# Irrigatron.net
KiCad netlist of a schematic drawn in EasyEDA
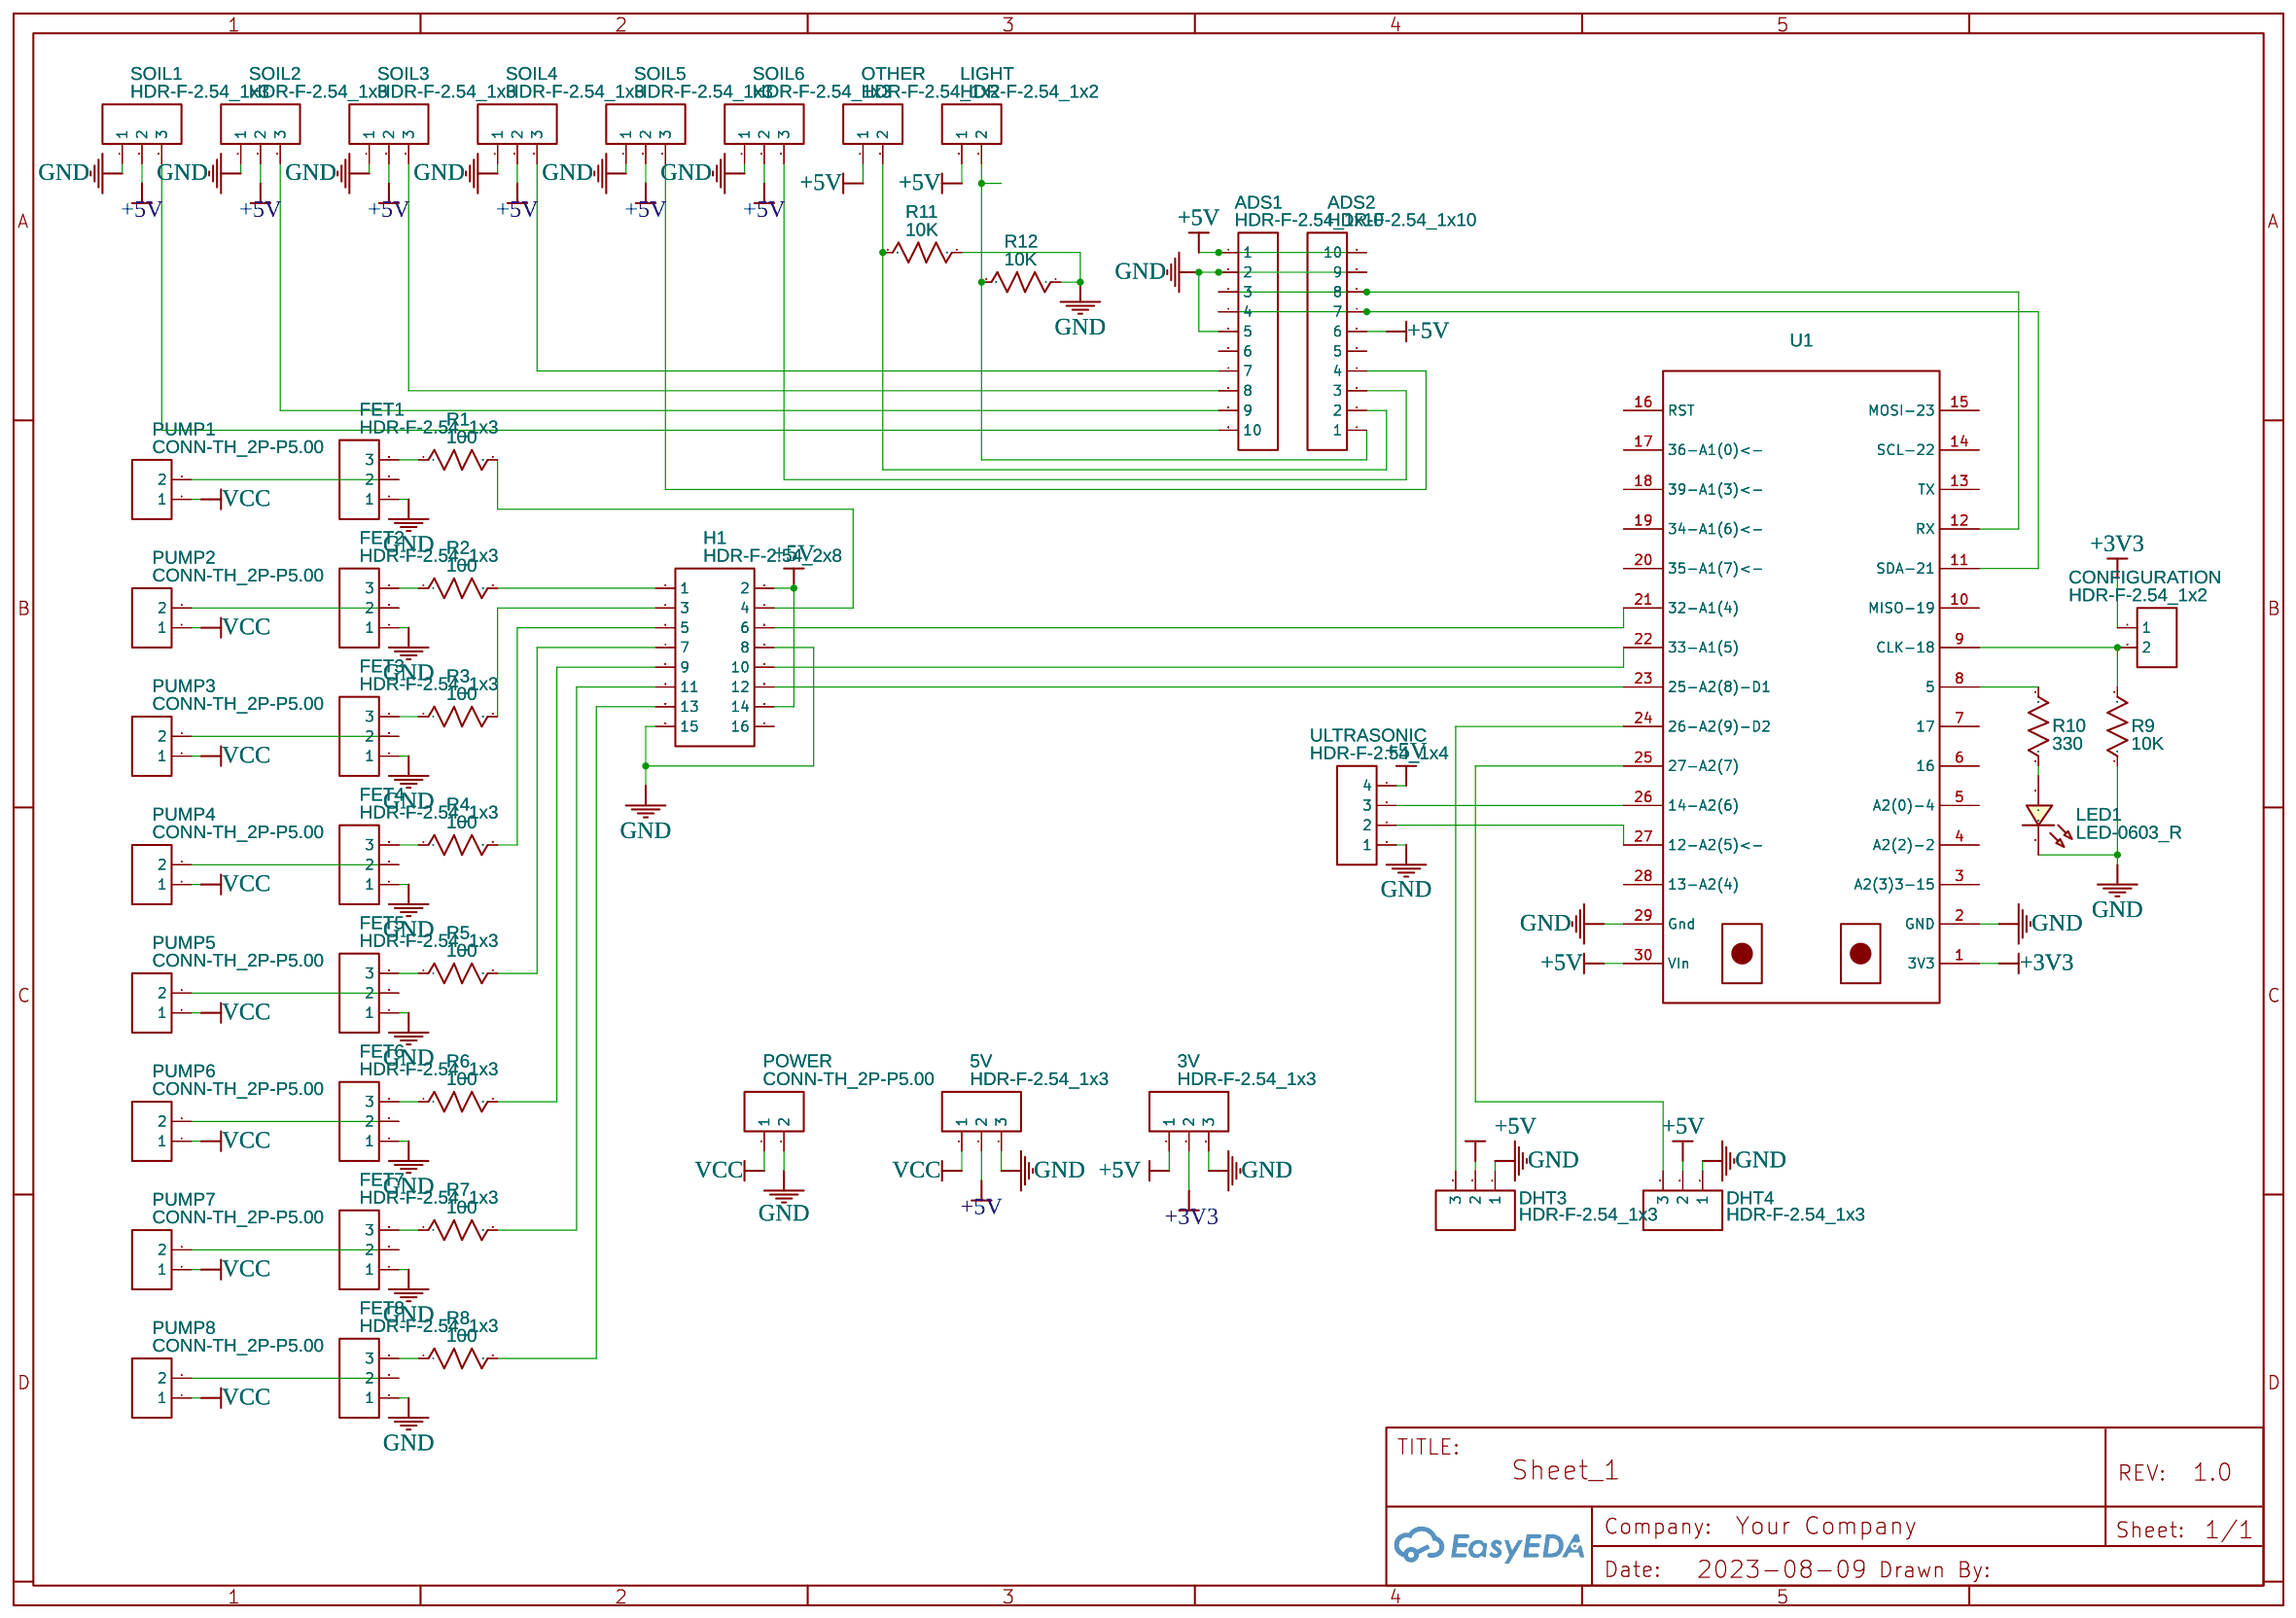
[diagram p0: schematic sheet]

(export (version "E")
  (design (tool "Eeschema 10.0.6"))
  (components
    (comp (ref "3V") (value "HDR-F-2.54_1x3") (libsource (lib "") (part "HDR-F-2.54_1x3_4")))
    (comp (ref "5V") (value "HDR-F-2.54_1x3") (libsource (lib "") (part "HDR-F-2.54_1x3_3")))
    (comp (ref "ADS1") (value "HDR-F-2.54_1x10") (libsource (lib "") (part "HDR-F-2.54_1x10")))
    (comp (ref "ADS2") (value "HDR-F-2.54_1x10") (libsource (lib "") (part "HDR-F-2.54_1x10_1")))
    (comp (ref "CONFIGURATION") (value "HDR-F-2.54_1x2") (libsource (lib "") (part "HDR-F-2.54_1x2_1")))
    (comp (ref "DHT3") (value "HDR-F-2.54_1x3") (libsource (lib "") (part "HDR-F-2.54_1x3")))
    (comp (ref "DHT4") (value "HDR-F-2.54_1x3") (libsource (lib "") (part "HDR-F-2.54_1x3")))
    (comp (ref "FET1") (value "HDR-F-2.54_1x3") (libsource (lib "") (part "HDR-F-2.54_1x3_1")))
    (comp (ref "FET2") (value "HDR-F-2.54_1x3") (libsource (lib "") (part "HDR-F-2.54_1x3_1")))
    (comp (ref "FET3") (value "HDR-F-2.54_1x3") (libsource (lib "") (part "HDR-F-2.54_1x3_1")))
    (comp (ref "FET4") (value "HDR-F-2.54_1x3") (libsource (lib "") (part "HDR-F-2.54_1x3_1")))
    (comp (ref "FET5") (value "HDR-F-2.54_1x3") (libsource (lib "") (part "HDR-F-2.54_1x3_1")))
    (comp (ref "FET6") (value "HDR-F-2.54_1x3") (libsource (lib "") (part "HDR-F-2.54_1x3_1")))
    (comp (ref "FET7") (value "HDR-F-2.54_1x3") (libsource (lib "") (part "HDR-F-2.54_1x3_1")))
    (comp (ref "FET8") (value "HDR-F-2.54_1x3") (libsource (lib "") (part "HDR-F-2.54_1x3_1")))
    (comp (ref "H1") (value "HDR-F-2.54_2x8") (libsource (lib "") (part "HDR-F-2.54_2x8")))
    (comp (ref "LED1")
      (value "LED-0603_R")
      (fields
        (field (name "Manufacturer Part") "19-217/R6C-AL1M2VY/3T")
        (field (name "Manufacturer") "EVERLIGHT(台湾亿光)")
      )
      (libsource (lib "") (part "LED-0603_R"))
    )
    (comp (ref "LIGHT") (value "HDR-F-2.54_1x2") (libsource (lib "") (part "HDR-F-2.54_1x2")))
    (comp (ref "OTHER") (value "HDR-F-2.54_1x2") (libsource (lib "") (part "HDR-F-2.54_1x2_2")))
    (comp (ref "POWER") (value "CONN-TH_2P-P5.00") (libsource (lib "") (part "CONN-TH_2P-P5.00_1")))
    (comp (ref "PUMP1") (value "CONN-TH_2P-P5.00") (libsource (lib "") (part "CONN-TH_2P-P5.00")))
    (comp (ref "PUMP2") (value "CONN-TH_2P-P5.00") (libsource (lib "") (part "CONN-TH_2P-P5.00")))
    (comp (ref "PUMP3") (value "CONN-TH_2P-P5.00") (libsource (lib "") (part "CONN-TH_2P-P5.00")))
    (comp (ref "PUMP4") (value "CONN-TH_2P-P5.00") (libsource (lib "") (part "CONN-TH_2P-P5.00")))
    (comp (ref "PUMP5") (value "CONN-TH_2P-P5.00") (libsource (lib "") (part "CONN-TH_2P-P5.00")))
    (comp (ref "PUMP6") (value "CONN-TH_2P-P5.00") (libsource (lib "") (part "CONN-TH_2P-P5.00")))
    (comp (ref "PUMP7") (value "CONN-TH_2P-P5.00") (libsource (lib "") (part "CONN-TH_2P-P5.00")))
    (comp (ref "PUMP8") (value "CONN-TH_2P-P5.00") (libsource (lib "") (part "CONN-TH_2P-P5.00")))
    (comp (ref "R1") (value "100") (libsource (lib "") (part "R_0603_US_2")))
    (comp (ref "R2") (value "100") (libsource (lib "") (part "R_0603_US_2")))
    (comp (ref "R3") (value "100") (libsource (lib "") (part "R_0603_US_2")))
    (comp (ref "R4") (value "100") (libsource (lib "") (part "R_0603_US_2")))
    (comp (ref "R5") (value "100") (libsource (lib "") (part "R_0603_US_2")))
    (comp (ref "R6") (value "100") (libsource (lib "") (part "R_0603_US_2")))
    (comp (ref "R7") (value "100") (libsource (lib "") (part "R_0603_US_2")))
    (comp (ref "R8") (value "100") (libsource (lib "") (part "R_0603_US_2")))
    (comp (ref "R9") (value "10K") (libsource (lib "") (part "R_0603_US")))
    (comp (ref "R10") (value "330") (libsource (lib "") (part "R_0603_US")))
    (comp (ref "R11") (value "10K") (libsource (lib "") (part "R_0603_US_1")))
    (comp (ref "R12") (value "10K") (libsource (lib "") (part "R_0603_US_1")))
    (comp (ref "SOIL1") (value "HDR-F-2.54_1x3") (libsource (lib "") (part "HDR-F-2.54_1x3_2")))
    (comp (ref "SOIL2") (value "HDR-F-2.54_1x3") (libsource (lib "") (part "HDR-F-2.54_1x3_2")))
    (comp (ref "SOIL3") (value "HDR-F-2.54_1x3") (libsource (lib "") (part "HDR-F-2.54_1x3_2")))
    (comp (ref "SOIL4") (value "HDR-F-2.54_1x3") (libsource (lib "") (part "HDR-F-2.54_1x3_2")))
    (comp (ref "SOIL5") (value "HDR-F-2.54_1x3") (libsource (lib "") (part "HDR-F-2.54_1x3_2")))
    (comp (ref "SOIL6") (value "HDR-F-2.54_1x3") (libsource (lib "") (part "HDR-F-2.54_1x3_2")))
    (comp (ref "U1") (value "NO") (libsource (lib "") (part "DOIT ESP32 DEVKIT V1 (30pins)")))
    (comp (ref "ULTRASONIC") (value "HDR-F-2.54_1x4") (libsource (lib "") (part "HDR-F-2.54_1x4")))
  )
  (nets
    (net (code "1") (name "+3V3") (class "Default")
      (node (ref "3V") (pin "2") (pinfunction "2_2") (pintype "input"))
      (node (ref "CONFIGURATION") (pin "1") (pinfunction "1_1") (pintype "input"))
      (node (ref "U1") (pin "1") (pinfunction "3V3_1") (pintype "unspecified"))
    )
    (net (code "2") (name "+5V") (class "Default")
      (node (ref "3V") (pin "1") (pinfunction "1_1") (pintype "input"))
      (node (ref "5V") (pin "2") (pinfunction "2_2") (pintype "input"))
      (node (ref "ADS1") (pin "1") (pinfunction "1_1") (pintype "unspecified"))
      (node (ref "ADS2") (pin "10") (pinfunction "10_10") (pintype "unspecified"))
      (node (ref "ADS2") (pin "6") (pinfunction "6_6") (pintype "unspecified"))
      (node (ref "DHT3") (pin "2") (pinfunction "2_2") (pintype "input"))
      (node (ref "DHT4") (pin "2") (pinfunction "2_2") (pintype "input"))
      (node (ref "H1") (pin "14") (pinfunction "14_14") (pintype "input"))
      (node (ref "H1") (pin "2") (pinfunction "2_2") (pintype "input"))
      (node (ref "LIGHT") (pin "1") (pinfunction "1_1") (pintype "input"))
      (node (ref "OTHER") (pin "1") (pinfunction "1_1") (pintype "input"))
      (node (ref "SOIL1") (pin "2") (pinfunction "2_2") (pintype "input"))
      (node (ref "SOIL2") (pin "2") (pinfunction "2_2") (pintype "input"))
      (node (ref "SOIL3") (pin "2") (pinfunction "2_2") (pintype "input"))
      (node (ref "SOIL4") (pin "2") (pinfunction "2_2") (pintype "input"))
      (node (ref "SOIL5") (pin "2") (pinfunction "2_2") (pintype "input"))
      (node (ref "SOIL6") (pin "2") (pinfunction "2_2") (pintype "input"))
      (node (ref "U1") (pin "30") (pinfunction "VIn_30") (pintype "unspecified"))
      (node (ref "ULTRASONIC") (pin "4") (pinfunction "4_4") (pintype "unspecified"))
    )
    (net (code "3") (name "GND") (class "Default")
      (node (ref "3V") (pin "3") (pinfunction "3_3") (pintype "input"))
      (node (ref "5V") (pin "3") (pinfunction "3_3") (pintype "input"))
      (node (ref "ADS1") (pin "2") (pinfunction "2_2") (pintype "unspecified"))
      (node (ref "ADS1") (pin "5") (pinfunction "5_5") (pintype "unspecified"))
      (node (ref "ADS2") (pin "9") (pinfunction "9_9") (pintype "unspecified"))
      (node (ref "DHT3") (pin "1") (pinfunction "1_1") (pintype "input"))
      (node (ref "DHT4") (pin "1") (pinfunction "1_1") (pintype "input"))
      (node (ref "FET1") (pin "1") (pinfunction "1_1") (pintype "input"))
      (node (ref "FET2") (pin "1") (pinfunction "1_1") (pintype "input"))
      (node (ref "FET3") (pin "1") (pinfunction "1_1") (pintype "input"))
      (node (ref "FET4") (pin "1") (pinfunction "1_1") (pintype "input"))
      (node (ref "FET5") (pin "1") (pinfunction "1_1") (pintype "input"))
      (node (ref "FET6") (pin "1") (pinfunction "1_1") (pintype "input"))
      (node (ref "FET7") (pin "1") (pinfunction "1_1") (pintype "input"))
      (node (ref "FET8") (pin "1") (pinfunction "1_1") (pintype "input"))
      (node (ref "H1") (pin "15") (pinfunction "15_15") (pintype "input"))
      (node (ref "H1") (pin "8") (pinfunction "8_8") (pintype "input"))
      (node (ref "LED1") (pin "2") (pinfunction "2_2") (pintype "unspecified"))
      (node (ref "POWER") (pin "2") (pinfunction "2_2") (pintype "unspecified"))
      (node (ref "R11") (pin "1") (pinfunction "1_1") (pintype "unspecified"))
      (node (ref "R12") (pin "1") (pinfunction "1_1") (pintype "unspecified"))
      (node (ref "R9") (pin "1") (pinfunction "1_1") (pintype "unspecified"))
      (node (ref "SOIL1") (pin "1") (pinfunction "1_1") (pintype "input"))
      (node (ref "SOIL2") (pin "1") (pinfunction "1_1") (pintype "input"))
      (node (ref "SOIL3") (pin "1") (pinfunction "1_1") (pintype "input"))
      (node (ref "SOIL4") (pin "1") (pinfunction "1_1") (pintype "input"))
      (node (ref "SOIL5") (pin "1") (pinfunction "1_1") (pintype "input"))
      (node (ref "SOIL6") (pin "1") (pinfunction "1_1") (pintype "input"))
      (node (ref "U1") (pin "2") (pinfunction "GND_2") (pintype "unspecified"))
      (node (ref "U1") (pin "29") (pinfunction "Gnd_29") (pintype "unspecified"))
      (node (ref "ULTRASONIC") (pin "1") (pinfunction "1_1") (pintype "unspecified"))
    )
    (net (code "4") (name "Net-(ADS1-Pad7)") (class "Default")
      (node (ref "ADS1") (pin "7") (pinfunction "7_7") (pintype "unspecified"))
      (node (ref "SOIL4") (pin "3") (pinfunction "3_3") (pintype "input"))
    )
    (net (code "5") (name "Net-(ADS1-Pad8)") (class "Default")
      (node (ref "ADS1") (pin "8") (pinfunction "8_8") (pintype "unspecified"))
      (node (ref "SOIL3") (pin "3") (pinfunction "3_3") (pintype "input"))
    )
    (net (code "6") (name "Net-(ADS1-Pad9)") (class "Default")
      (node (ref "ADS1") (pin "9") (pinfunction "9_9") (pintype "unspecified"))
      (node (ref "SOIL2") (pin "3") (pinfunction "3_3") (pintype "input"))
    )
    (net (code "7") (name "Net-(ADS1-Pad10)") (class "Default")
      (node (ref "ADS1") (pin "10") (pinfunction "10_10") (pintype "unspecified"))
      (node (ref "SOIL1") (pin "3") (pinfunction "3_3") (pintype "input"))
    )
    (net (code "8") (name "Net-(ADS2-Pad1)") (class "Default")
      (node (ref "ADS2") (pin "1") (pinfunction "1_1") (pintype "unspecified"))
      (node (ref "LIGHT") (pin "2") (pinfunction "2_2") (pintype "input"))
      (node (ref "R12") (pin "2") (pinfunction "2_2") (pintype "unspecified"))
    )
    (net (code "9") (name "Net-(ADS2-Pad2)") (class "Default")
      (node (ref "ADS2") (pin "2") (pinfunction "2_2") (pintype "unspecified"))
      (node (ref "OTHER") (pin "2") (pinfunction "2_2") (pintype "input"))
      (node (ref "R11") (pin "2") (pinfunction "2_2") (pintype "unspecified"))
    )
    (net (code "10") (name "Net-(ADS2-Pad3)") (class "Default")
      (node (ref "ADS2") (pin "3") (pinfunction "3_3") (pintype "unspecified"))
      (node (ref "SOIL6") (pin "3") (pinfunction "3_3") (pintype "input"))
    )
    (net (code "11") (name "Net-(ADS2-Pad4)") (class "Default")
      (node (ref "ADS2") (pin "4") (pinfunction "4_4") (pintype "unspecified"))
      (node (ref "SOIL5") (pin "3") (pinfunction "3_3") (pintype "input"))
    )
    (net (code "12") (name "Net-(FET1-Pad2)") (class "Default")
      (node (ref "FET1") (pin "2") (pinfunction "2_2") (pintype "input"))
      (node (ref "PUMP1") (pin "2") (pinfunction "2_2") (pintype "unspecified"))
    )
    (net (code "13") (name "Net-(FET1-Pad3)") (class "Default")
      (node (ref "FET1") (pin "3") (pinfunction "3_3") (pintype "input"))
      (node (ref "R1") (pin "1") (pinfunction "1_1") (pintype "unspecified"))
    )
    (net (code "14") (name "Net-(FET2-Pad2)") (class "Default")
      (node (ref "FET2") (pin "2") (pinfunction "2_2") (pintype "input"))
      (node (ref "PUMP2") (pin "2") (pinfunction "2_2") (pintype "unspecified"))
    )
    (net (code "15") (name "Net-(FET2-Pad3)") (class "Default")
      (node (ref "FET2") (pin "3") (pinfunction "3_3") (pintype "input"))
      (node (ref "R2") (pin "1") (pinfunction "1_1") (pintype "unspecified"))
    )
    (net (code "16") (name "Net-(FET3-Pad3)") (class "Default")
      (node (ref "FET3") (pin "3") (pinfunction "3_3") (pintype "input"))
      (node (ref "R3") (pin "1") (pinfunction "1_1") (pintype "unspecified"))
    )
    (net (code "17") (name "Net-(FET4-Pad2)") (class "Default")
      (node (ref "FET4") (pin "2") (pinfunction "2_2") (pintype "input"))
      (node (ref "PUMP4") (pin "2") (pinfunction "2_2") (pintype "unspecified"))
    )
    (net (code "18") (name "Net-(FET4-Pad3)") (class "Default")
      (node (ref "FET4") (pin "3") (pinfunction "3_3") (pintype "input"))
      (node (ref "R4") (pin "1") (pinfunction "1_1") (pintype "unspecified"))
    )
    (net (code "19") (name "Net-(FET5-Pad2)") (class "Default")
      (node (ref "FET5") (pin "2") (pinfunction "2_2") (pintype "input"))
      (node (ref "PUMP5") (pin "2") (pinfunction "2_2") (pintype "unspecified"))
    )
    (net (code "20") (name "Net-(FET5-Pad3)") (class "Default")
      (node (ref "FET5") (pin "3") (pinfunction "3_3") (pintype "input"))
      (node (ref "R5") (pin "1") (pinfunction "1_1") (pintype "unspecified"))
    )
    (net (code "21") (name "Net-(FET6-Pad2)") (class "Default")
      (node (ref "FET6") (pin "2") (pinfunction "2_2") (pintype "input"))
      (node (ref "PUMP6") (pin "2") (pinfunction "2_2") (pintype "unspecified"))
    )
    (net (code "22") (name "Net-(FET6-Pad3)") (class "Default")
      (node (ref "FET6") (pin "3") (pinfunction "3_3") (pintype "input"))
      (node (ref "R6") (pin "1") (pinfunction "1_1") (pintype "unspecified"))
    )
    (net (code "23") (name "Net-(FET7-Pad2)") (class "Default")
      (node (ref "FET7") (pin "2") (pinfunction "2_2") (pintype "input"))
      (node (ref "PUMP7") (pin "2") (pinfunction "2_2") (pintype "unspecified"))
    )
    (net (code "24") (name "Net-(FET7-Pad3)") (class "Default")
      (node (ref "FET7") (pin "3") (pinfunction "3_3") (pintype "input"))
      (node (ref "R7") (pin "1") (pinfunction "1_1") (pintype "unspecified"))
    )
    (net (code "25") (name "Net-(FET8-Pad2)") (class "Default")
      (node (ref "FET8") (pin "2") (pinfunction "2_2") (pintype "input"))
      (node (ref "PUMP8") (pin "2") (pinfunction "2_2") (pintype "unspecified"))
    )
    (net (code "26") (name "Net-(FET8-Pad3)") (class "Default")
      (node (ref "FET8") (pin "3") (pinfunction "3_3") (pintype "input"))
      (node (ref "R8") (pin "1") (pinfunction "1_1") (pintype "unspecified"))
    )
    (net (code "27") (name "Net-(H1-Pad1)") (class "Default")
      (node (ref "H1") (pin "1") (pinfunction "1_1") (pintype "input"))
      (node (ref "R2") (pin "2") (pinfunction "2_2") (pintype "unspecified"))
    )
    (net (code "28") (name "Net-(H1-Pad3)") (class "Default")
      (node (ref "H1") (pin "3") (pinfunction "3_3") (pintype "input"))
      (node (ref "R3") (pin "2") (pinfunction "2_2") (pintype "unspecified"))
    )
    (net (code "29") (name "Net-(H1-Pad4)") (class "Default")
      (node (ref "H1") (pin "4") (pinfunction "4_4") (pintype "input"))
      (node (ref "R1") (pin "2") (pinfunction "2_2") (pintype "unspecified"))
    )
    (net (code "30") (name "Net-(H1-Pad5)") (class "Default")
      (node (ref "H1") (pin "5") (pinfunction "5_5") (pintype "input"))
      (node (ref "R4") (pin "2") (pinfunction "2_2") (pintype "unspecified"))
    )
    (net (code "31") (name "Net-(H1-Pad7)") (class "Default")
      (node (ref "H1") (pin "7") (pinfunction "7_7") (pintype "input"))
      (node (ref "R5") (pin "2") (pinfunction "2_2") (pintype "unspecified"))
    )
    (net (code "32") (name "Net-(H1-Pad9)") (class "Default")
      (node (ref "H1") (pin "9") (pinfunction "9_9") (pintype "input"))
      (node (ref "R6") (pin "2") (pinfunction "2_2") (pintype "unspecified"))
    )
    (net (code "33") (name "Net-(H1-Pad11)") (class "Default")
      (node (ref "H1") (pin "11") (pinfunction "11_11") (pintype "input"))
      (node (ref "R7") (pin "2") (pinfunction "2_2") (pintype "unspecified"))
    )
    (net (code "34") (name "Net-(H1-Pad13)") (class "Default")
      (node (ref "H1") (pin "13") (pinfunction "13_13") (pintype "input"))
      (node (ref "R8") (pin "2") (pinfunction "2_2") (pintype "unspecified"))
    )
    (net (code "35") (name "Net-(LED1-Pad1)") (class "Default")
      (node (ref "LED1") (pin "1") (pinfunction "1_1") (pintype "unspecified"))
      (node (ref "R10") (pin "1") (pinfunction "1_1") (pintype "unspecified"))
    )
    (net (code "36") (name "Net-(U1-5)") (class "Default")
      (node (ref "R10") (pin "2") (pinfunction "2_2") (pintype "unspecified"))
      (node (ref "U1") (pin "8") (pinfunction "5_8") (pintype "unspecified"))
    )
    (net (code "37") (name "Net-(U1-12-A2(5)<-)") (class "Default")
      (node (ref "U1") (pin "27") (pinfunction "12-A2(5)<-_27") (pintype "unspecified"))
      (node (ref "ULTRASONIC") (pin "2") (pinfunction "2_2") (pintype "unspecified"))
    )
    (net (code "38") (name "Net-(U1-14-A2(6))") (class "Default")
      (node (ref "U1") (pin "26") (pinfunction "14-A2(6)_26") (pintype "unspecified"))
      (node (ref "ULTRASONIC") (pin "3") (pinfunction "3_3") (pintype "unspecified"))
    )
    (net (code "39") (name "Net-(U1-25-A2(8)-D1)") (class "Default")
      (node (ref "H1") (pin "12") (pinfunction "12_12") (pintype "input"))
      (node (ref "U1") (pin "23") (pinfunction "25-A2(8)-D1_23") (pintype "unspecified"))
    )
    (net (code "40") (name "Net-(U1-26-A2(9)-D2)") (class "Default")
      (node (ref "DHT3") (pin "3") (pinfunction "3_3") (pintype "input"))
      (node (ref "U1") (pin "24") (pinfunction "26-A2(9)-D2_24") (pintype "unspecified"))
    )
    (net (code "41") (name "Net-(U1-27-A2(7))") (class "Default")
      (node (ref "DHT4") (pin "3") (pinfunction "3_3") (pintype "input"))
      (node (ref "U1") (pin "25") (pinfunction "27-A2(7)_25") (pintype "unspecified"))
    )
    (net (code "42") (name "Net-(U1-32-A1(4))") (class "Default")
      (node (ref "H1") (pin "6") (pinfunction "6_6") (pintype "input"))
      (node (ref "U1") (pin "21") (pinfunction "32-A1(4)_21") (pintype "unspecified"))
    )
    (net (code "43") (name "Net-(U1-33-A1(5))") (class "Default")
      (node (ref "H1") (pin "10") (pinfunction "10_10") (pintype "input"))
      (node (ref "U1") (pin "22") (pinfunction "33-A1(5)_22") (pintype "unspecified"))
    )
    (net (code "44") (name "Net-(U1-CLK-18)") (class "Default")
      (node (ref "CONFIGURATION") (pin "2") (pinfunction "2_2") (pintype "input"))
      (node (ref "R9") (pin "2") (pinfunction "2_2") (pintype "unspecified"))
      (node (ref "U1") (pin "9") (pinfunction "CLK-18_9") (pintype "unspecified"))
    )
    (net (code "45") (name "Net-(U1-RX)") (class "Default")
      (node (ref "ADS1") (pin "3") (pinfunction "3_3") (pintype "unspecified"))
      (node (ref "ADS2") (pin "8") (pinfunction "8_8") (pintype "unspecified"))
      (node (ref "U1") (pin "12") (pinfunction "RX_12") (pintype "unspecified"))
    )
    (net (code "46") (name "Net-(U1-SDA-21)") (class "Default")
      (node (ref "ADS1") (pin "4") (pinfunction "4_4") (pintype "unspecified"))
      (node (ref "ADS2") (pin "7") (pinfunction "7_7") (pintype "unspecified"))
      (node (ref "U1") (pin "11") (pinfunction "SDA-21_11") (pintype "unspecified"))
    )
    (net (code "47") (name "VCC") (class "Default")
      (node (ref "5V") (pin "1") (pinfunction "1_1") (pintype "input"))
      (node (ref "POWER") (pin "1") (pinfunction "1_1") (pintype "unspecified"))
      (node (ref "PUMP1") (pin "1") (pinfunction "1_1") (pintype "unspecified"))
      (node (ref "PUMP2") (pin "1") (pinfunction "1_1") (pintype "unspecified"))
      (node (ref "PUMP3") (pin "1") (pinfunction "1_1") (pintype "unspecified"))
      (node (ref "PUMP4") (pin "1") (pinfunction "1_1") (pintype "unspecified"))
      (node (ref "PUMP5") (pin "1") (pinfunction "1_1") (pintype "unspecified"))
      (node (ref "PUMP6") (pin "1") (pinfunction "1_1") (pintype "unspecified"))
      (node (ref "PUMP7") (pin "1") (pinfunction "1_1") (pintype "unspecified"))
      (node (ref "PUMP8") (pin "1") (pinfunction "1_1") (pintype "unspecified"))
    )
    (net (code "48") (name "unconnected-(ADS1-Pad6)") (class "Default")
      (node (ref "ADS1") (pin "6") (pinfunction "6_6") (pintype "unspecified"))
    )
    (net (code "49") (name "unconnected-(ADS2-Pad5)") (class "Default")
      (node (ref "ADS2") (pin "5") (pinfunction "5_5") (pintype "unspecified"))
    )
    (net (code "50") (name "unconnected-(FET3-Pad2)") (class "Default")
      (node (ref "FET3") (pin "2") (pinfunction "2_2") (pintype "input"))
    )
    (net (code "51") (name "unconnected-(H1-Pad16)") (class "Default")
      (node (ref "H1") (pin "16") (pinfunction "16_16") (pintype "input"))
    )
    (net (code "52") (name "unconnected-(PUMP3-Pad2)") (class "Default")
      (node (ref "PUMP3") (pin "2") (pinfunction "2_2") (pintype "unspecified"))
    )
    (net (code "53") (name "unconnected-(U1-13-A2(4)-Pad28)") (class "Default")
      (node (ref "U1") (pin "28") (pinfunction "13-A2(4)_28") (pintype "unspecified"))
    )
    (net (code "54") (name "unconnected-(U1-16-Pad6)") (class "Default")
      (node (ref "U1") (pin "6") (pinfunction "16_6") (pintype "unspecified"))
    )
    (net (code "55") (name "unconnected-(U1-17-Pad7)") (class "Default")
      (node (ref "U1") (pin "7") (pinfunction "17_7") (pintype "unspecified"))
    )
    (net (code "56") (name "unconnected-(U1-34-A1(6)<--Pad19)") (class "Default")
      (node (ref "U1") (pin "19") (pinfunction "34-A1(6)<-_19") (pintype "unspecified"))
    )
    (net (code "57") (name "unconnected-(U1-35-A1(7)<--Pad20)") (class "Default")
      (node (ref "U1") (pin "20") (pinfunction "35-A1(7)<-_20") (pintype "unspecified"))
    )
    (net (code "58") (name "unconnected-(U1-36-A1(0)<--Pad17)") (class "Default")
      (node (ref "U1") (pin "17") (pinfunction "36-A1(0)<-_17") (pintype "unspecified"))
    )
    (net (code "59") (name "unconnected-(U1-39-A1(3)<--Pad18)") (class "Default")
      (node (ref "U1") (pin "18") (pinfunction "39-A1(3)<-_18") (pintype "unspecified"))
    )
    (net (code "60") (name "unconnected-(U1-A2(0)-4-Pad5)") (class "Default")
      (node (ref "U1") (pin "5") (pinfunction "A2(0)-4_5") (pintype "unspecified"))
    )
    (net (code "61") (name "unconnected-(U1-A2(2)-2-Pad4)") (class "Default")
      (node (ref "U1") (pin "4") (pinfunction "A2(2)-2_4") (pintype "unspecified"))
    )
    (net (code "62") (name "unconnected-(U1-A2(3)3-15-Pad3)") (class "Default")
      (node (ref "U1") (pin "3") (pinfunction "A2(3)3-15_3") (pintype "unspecified"))
    )
    (net (code "63") (name "unconnected-(U1-MISO-19-Pad10)") (class "Default")
      (node (ref "U1") (pin "10") (pinfunction "MISO-19_10") (pintype "unspecified"))
    )
    (net (code "64") (name "unconnected-(U1-MOSI-23-Pad15)") (class "Default")
      (node (ref "U1") (pin "15") (pinfunction "MOSI-23_15") (pintype "unspecified"))
    )
    (net (code "65") (name "unconnected-(U1-RST-Pad16)") (class "Default")
      (node (ref "U1") (pin "16") (pinfunction "RST_16") (pintype "unspecified"))
    )
    (net (code "66") (name "unconnected-(U1-SCL-22-Pad14)") (class "Default")
      (node (ref "U1") (pin "14") (pinfunction "SCL-22_14") (pintype "unspecified"))
    )
    (net (code "67") (name "unconnected-(U1-TX-Pad13)") (class "Default")
      (node (ref "U1") (pin "13") (pinfunction "TX_13") (pintype "unspecified"))
    )
  )
)
